# pactec_version_rev_A.net
KiCad netlist of a schematic drawn in EAGLE
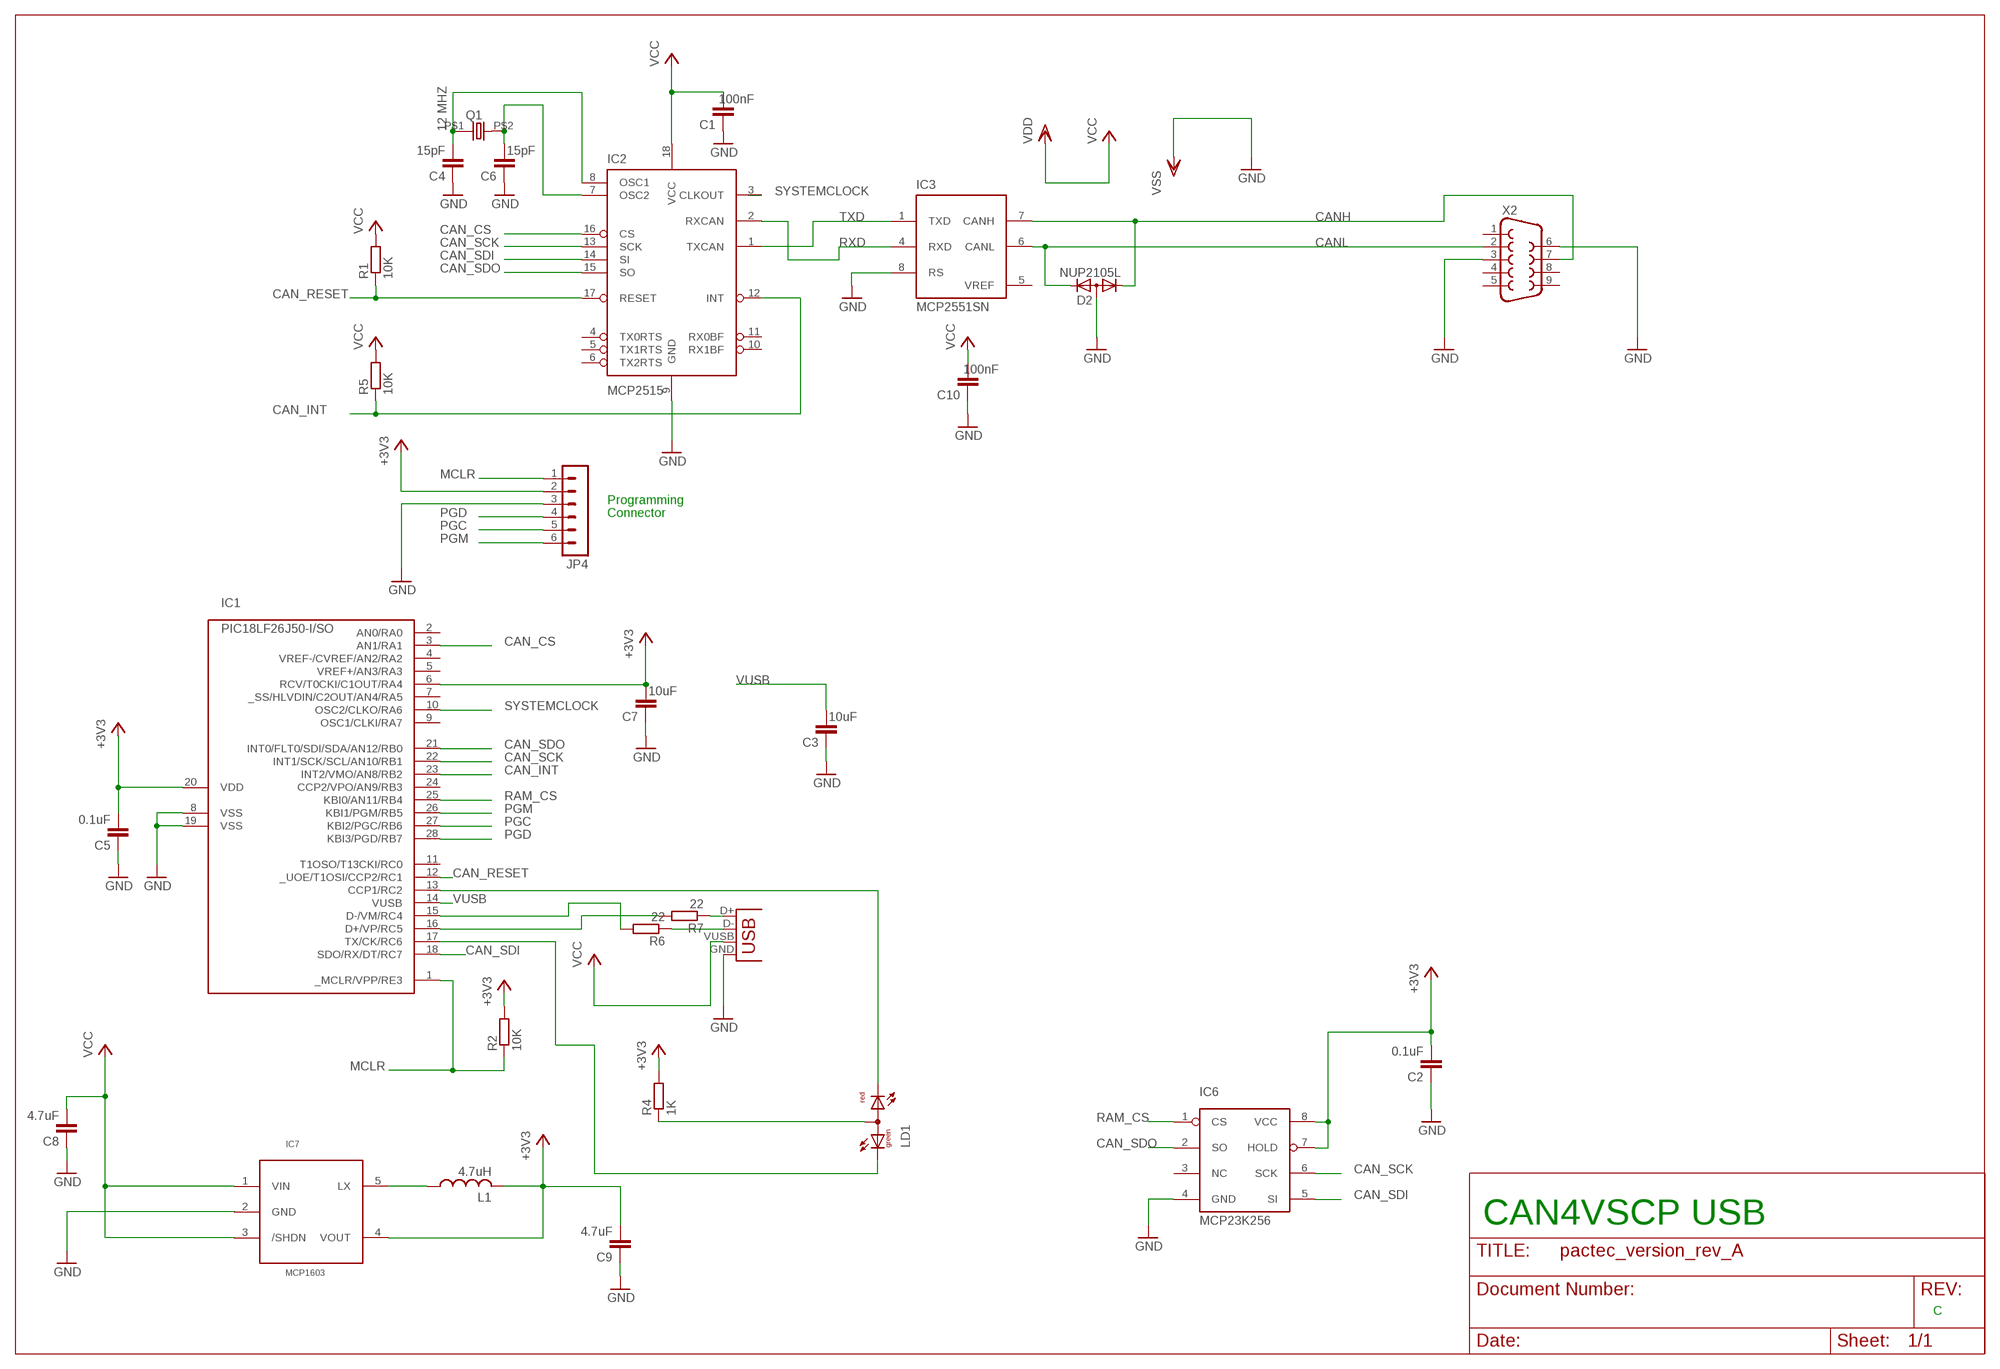
[diagram p0: schematic, sheet 1]

(export (version "E")
  (design (tool "Eeschema 10.0.6"))
  (components
    (comp (ref "C1")
      (value "100nF")
      (footprint "eagle-import:C0805")
      (libsource (lib "eagle-import") (part "C-EUC0805"))
    )
    (comp (ref "C2")
      (value "0.1uF")
      (footprint "eagle-import:C0805")
      (libsource (lib "eagle-import") (part "C-EUC0805"))
    )
    (comp (ref "C3")
      (value "10uF")
      (footprint "eagle-import:C0805")
      (libsource (lib "eagle-import") (part "C-EUC0805"))
    )
    (comp (ref "C4")
      (value "15pF")
      (footprint "eagle-import:C0805")
      (libsource (lib "eagle-import") (part "C-EUC0805"))
    )
    (comp (ref "C5")
      (value "0.1uF")
      (footprint "eagle-import:C0805")
      (libsource (lib "eagle-import") (part "C-EUC0805"))
    )
    (comp (ref "C6")
      (value "15pF")
      (footprint "eagle-import:C0805")
      (libsource (lib "eagle-import") (part "C-EUC0805"))
    )
    (comp (ref "C7")
      (value "10uF")
      (footprint "eagle-import:C0805")
      (libsource (lib "eagle-import") (part "C-EUC0805"))
    )
    (comp (ref "C8")
      (value "4.7uF")
      (footprint "eagle-import:C0805")
      (libsource (lib "eagle-import") (part "C-EUC0805"))
    )
    (comp (ref "C9")
      (value "4.7uF")
      (footprint "eagle-import:C0805")
      (libsource (lib "eagle-import") (part "C-EUC0805"))
    )
    (comp (ref "C10")
      (value "100nF")
      (footprint "eagle-import:C0805")
      (libsource (lib "eagle-import") (part "C-EUC0805"))
    )
    (comp (ref "D2")
      (value "NUP2105L")
      (footprint "eagle-import:SOT23")
      (libsource (lib "eagle-import") (part "DIODE-2CA|ACSOT23"))
    )
    (comp (ref "IC1")
      (value "PIC18LF26J50-I/SO")
      (footprint "eagle-import:SO-28W")
      (libsource (lib "eagle-import") (part "PIC182550-I/SOLF"))
    )
    (comp (ref "IC2")
      (value "MCP2515")
      (footprint "eagle-import:SO-18W")
      (libsource (lib "eagle-import") (part "MCP2515"))
    )
    (comp (ref "IC3")
      (value "MCP2551SN")
      (footprint "eagle-import:SO-08")
      (libsource (lib "eagle-import") (part "MCP2551SN"))
    )
    (comp (ref "IC6")
      (value "MCP23K256")
      (footprint "eagle-import:SO-8")
      (libsource (lib "eagle-import") (part "MCP23A256"))
    )
    (comp (ref "IC7")
      (value "MCP1603")
      (footprint "eagle-import:SOT23-5L")
      (libsource (lib "eagle-import") (part "MCP1603"))
    )
    (comp (ref "J4")
      (value "USB-B-S")
      (footprint "eagle-import:USB-B-SMT")
      (libsource (lib "eagle-import") (part "USB-B-S"))
    )
    (comp (ref "JP4")
      (value "MA06-1")
      (footprint "eagle-import:MA06-1")
      (libsource (lib "eagle-import") (part "MA06-1"))
    )
    (comp (ref "L1")
      (value "4.7uH")
      (footprint "eagle-import:L2012C")
      (libsource (lib "eagle-import") (part "L-USL2012C"))
    )
    (comp (ref "LD1")
      (value "DUOLED-RG-A")
      (footprint "eagle-import:DUOLED-A-5MM")
      (libsource (lib "eagle-import") (part "DUOLED-RG-A"))
    )
    (comp (ref "Q1")
      (value "12 MHZ")
      (footprint "eagle-import:9C")
      (libsource (lib "eagle-import") (part "HC-49S"))
    )
    (comp (ref "R1")
      (value "10K")
      (footprint "eagle-import:R0805")
      (libsource (lib "eagle-import") (part "R-EU_R0805"))
    )
    (comp (ref "R2")
      (value "10K")
      (footprint "eagle-import:R0805")
      (libsource (lib "eagle-import") (part "R-EU_R0805"))
    )
    (comp (ref "R4")
      (value "1K")
      (footprint "eagle-import:R0805")
      (libsource (lib "eagle-import") (part "R-EU_R0805"))
    )
    (comp (ref "R5")
      (value "10K")
      (footprint "eagle-import:R0805")
      (libsource (lib "eagle-import") (part "R-EU_R0805"))
    )
    (comp (ref "R6")
      (value "22")
      (footprint "eagle-import:R0805")
      (libsource (lib "eagle-import") (part "R-EU_R0805"))
    )
    (comp (ref "R7")
      (value "22")
      (footprint "eagle-import:R0805")
      (libsource (lib "eagle-import") (part "R-EU_R0805"))
    )
    (comp (ref "X2")
      (value "DB9MALE")
      (footprint "eagle-import:DB9_MALE")
      (libsource (lib "eagle-import") (part "DB9MALE"))
    )
  )
  (nets
    (net (code "1") (name "+3V3") (class "Default")
      (node (ref "C2") (pin "2") (pinfunction "2_2") (pintype "passive"))
      (node (ref "C5") (pin "2") (pinfunction "2_2") (pintype "passive"))
      (node (ref "C7") (pin "2") (pinfunction "2_2") (pintype "passive"))
      (node (ref "C9") (pin "2") (pinfunction "2_2") (pintype "passive"))
      (node (ref "IC1") (pin "20") (pinfunction "VDD_20") (pintype "power_in"))
      (node (ref "IC1") (pin "6") (pinfunction "RCV/T0CKI/C1OUT/RA4_6") (pintype "bidirectional"))
      (node (ref "IC6") (pin "7") (pinfunction "HOLD_7") (pintype "input"))
      (node (ref "IC6") (pin "8") (pinfunction "VCC_8") (pintype "power_in"))
      (node (ref "IC7") (pin "4") (pinfunction "VOUT_4") (pintype "bidirectional"))
      (node (ref "JP4") (pin "2") (pinfunction "2_2") (pintype "passive"))
      (node (ref "L1") (pin "2") (pinfunction "2_2") (pintype "passive"))
      (node (ref "R2") (pin "2") (pinfunction "2_2") (pintype "passive"))
      (node (ref "R4") (pin "2") (pinfunction "2_2") (pintype "passive"))
    )
    (net (code "2") (name "/CANH") (class "Default")
      (node (ref "D2") (pin "1") (pinfunction "K1_1") (pintype "passive"))
      (node (ref "IC3") (pin "7") (pinfunction "CANH_7") (pintype "bidirectional"))
      (node (ref "X2") (pin "7") (pinfunction "7_7") (pintype "passive"))
    )
    (net (code "3") (name "/CANL") (class "Default")
      (node (ref "D2") (pin "2") (pinfunction "K2_2") (pintype "passive"))
      (node (ref "IC3") (pin "6") (pinfunction "CANL_6") (pintype "bidirectional"))
      (node (ref "X2") (pin "2") (pinfunction "2_2") (pintype "passive"))
    )
    (net (code "4") (name "/CAN_CS") (class "Default")
      (node (ref "IC1") (pin "3") (pinfunction "AN1/RA1_3") (pintype "bidirectional"))
      (node (ref "IC2") (pin "16") (pinfunction "CS_16") (pintype "input"))
    )
    (net (code "5") (name "/CAN_INT") (class "Default")
      (node (ref "IC1") (pin "23") (pinfunction "INT2/VMO/AN8/RB2_23") (pintype "bidirectional"))
      (node (ref "IC2") (pin "12") (pinfunction "INT_12") (pintype "output"))
      (node (ref "R5") (pin "1") (pinfunction "1_1") (pintype "passive"))
    )
    (net (code "6") (name "/CAN_RESET") (class "Default")
      (node (ref "IC1") (pin "12") (pinfunction "_UOE/T1OSI/CCP2/RC1_12") (pintype "bidirectional"))
      (node (ref "IC2") (pin "17") (pinfunction "RESET_17") (pintype "input"))
      (node (ref "R1") (pin "1") (pinfunction "1_1") (pintype "passive"))
    )
    (net (code "7") (name "/CAN_SCK") (class "Default")
      (node (ref "IC1") (pin "22") (pinfunction "INT1/SCK/SCL/AN10/RB1_22") (pintype "bidirectional"))
      (node (ref "IC2") (pin "13") (pinfunction "SCK_13") (pintype "input"))
      (node (ref "IC6") (pin "6") (pinfunction "SCK_6") (pintype "input"))
    )
    (net (code "8") (name "/CAN_SDI") (class "Default")
      (node (ref "IC1") (pin "18") (pinfunction "SDO/RX/DT/RC7_18") (pintype "bidirectional"))
      (node (ref "IC2") (pin "14") (pinfunction "SI_14") (pintype "input"))
      (node (ref "IC6") (pin "5") (pinfunction "SI_5") (pintype "input"))
    )
    (net (code "9") (name "/CAN_SDO") (class "Default")
      (node (ref "IC1") (pin "21") (pinfunction "INT0/FLT0/SDI/SDA/AN12/RB0_21") (pintype "bidirectional"))
      (node (ref "IC2") (pin "15") (pinfunction "SO_15") (pintype "output"))
      (node (ref "IC6") (pin "2") (pinfunction "SO_2") (pintype "output"))
    )
    (net (code "10") (name "/MCLR") (class "Default")
      (node (ref "IC1") (pin "1") (pinfunction "_MCLR/VPP/RE3_1") (pintype "input"))
      (node (ref "JP4") (pin "1") (pinfunction "1_1") (pintype "passive"))
      (node (ref "R2") (pin "1") (pinfunction "1_1") (pintype "passive"))
    )
    (net (code "11") (name "/PGC") (class "Default")
      (node (ref "IC1") (pin "27") (pinfunction "KBI2/PGC/RB6_27") (pintype "bidirectional"))
      (node (ref "JP4") (pin "5") (pinfunction "5_5") (pintype "passive"))
    )
    (net (code "12") (name "/PGD") (class "Default")
      (node (ref "IC1") (pin "28") (pinfunction "KBI3/PGD/RB7_28") (pintype "bidirectional"))
      (node (ref "JP4") (pin "4") (pinfunction "4_4") (pintype "passive"))
    )
    (net (code "13") (name "/PGM") (class "Default")
      (node (ref "IC1") (pin "26") (pinfunction "KBI1/PGM/RB5_26") (pintype "bidirectional"))
      (node (ref "JP4") (pin "6") (pinfunction "6_6") (pintype "passive"))
    )
    (net (code "14") (name "/RAM_CS") (class "Default")
      (node (ref "IC1") (pin "25") (pinfunction "KBI0/AN11/RB4_25") (pintype "bidirectional"))
      (node (ref "IC6") (pin "1") (pinfunction "CS_1") (pintype "input"))
    )
    (net (code "15") (name "/RXD") (class "Default")
      (node (ref "IC2") (pin "2") (pinfunction "RXCAN_2") (pintype "input"))
      (node (ref "IC3") (pin "4") (pinfunction "RXD_4") (pintype "output"))
    )
    (net (code "16") (name "/SYSTEMCLOCK") (class "Default")
      (node (ref "IC1") (pin "10") (pinfunction "OSC2/CLKO/RA6_10") (pintype "bidirectional"))
      (node (ref "IC2") (pin "3") (pinfunction "CLKOUT_3") (pintype "output"))
    )
    (net (code "17") (name "/TXD") (class "Default")
      (node (ref "IC2") (pin "1") (pinfunction "TXCAN_1") (pintype "output"))
      (node (ref "IC3") (pin "1") (pinfunction "TXD_1") (pintype "input"))
    )
    (net (code "18") (name "/VREF") (class "Default")
      (node (ref "IC3") (pin "5") (pinfunction "VREF_5") (pintype "power_in"))
    )
    (net (code "19") (name "/VUSB") (class "Default")
      (node (ref "C3") (pin "2") (pinfunction "2_2") (pintype "passive"))
      (node (ref "IC1") (pin "14") (pinfunction "VUSB_14") (pintype "bidirectional"))
    )
    (net (code "20") (name "GND") (class "Default")
      (node (ref "C1") (pin "1") (pinfunction "1_1") (pintype "passive"))
      (node (ref "C10") (pin "1") (pinfunction "1_1") (pintype "passive"))
      (node (ref "C2") (pin "1") (pinfunction "1_1") (pintype "passive"))
      (node (ref "C3") (pin "1") (pinfunction "1_1") (pintype "passive"))
      (node (ref "C4") (pin "1") (pinfunction "1_1") (pintype "passive"))
      (node (ref "C5") (pin "1") (pinfunction "1_1") (pintype "passive"))
      (node (ref "C6") (pin "1") (pinfunction "1_1") (pintype "passive"))
      (node (ref "C7") (pin "1") (pinfunction "1_1") (pintype "passive"))
      (node (ref "C8") (pin "1") (pinfunction "1_1") (pintype "passive"))
      (node (ref "C9") (pin "1") (pinfunction "1_1") (pintype "passive"))
      (node (ref "D2") (pin "3") (pinfunction "A_3") (pintype "passive"))
      (node (ref "IC1") (pin "19") (pinfunction "VSS_19") (pintype "power_in"))
      (node (ref "IC1") (pin "8") (pinfunction "VSS_8") (pintype "power_in"))
      (node (ref "IC2") (pin "9") (pinfunction "GND_9") (pintype "power_in"))
      (node (ref "IC3") (pin "8") (pinfunction "RS_8") (pintype "input"))
      (node (ref "IC6") (pin "4") (pinfunction "GND_4") (pintype "power_in"))
      (node (ref "IC7") (pin "2") (pinfunction "GND_2") (pintype "power_in"))
      (node (ref "J4") (pin "GND") (pinfunction "GND_GND") (pintype "bidirectional"))
      (node (ref "JP4") (pin "3") (pinfunction "3_3") (pintype "passive"))
      (node (ref "X2") (pin "3") (pinfunction "3_3") (pintype "passive"))
      (node (ref "X2") (pin "6") (pinfunction "6_6") (pintype "passive"))
    )
    (net (code "21") (name "Net-(IC1-CCP1{slash}RC2)") (class "Default")
      (node (ref "IC1") (pin "13") (pinfunction "CCP1/RC2_13") (pintype "bidirectional"))
      (node (ref "LD1") (pin "CR") (pinfunction "CR_CR") (pintype "passive"))
    )
    (net (code "22") (name "Net-(IC1-D+{slash}VP{slash}RC5)") (class "Default")
      (node (ref "IC1") (pin "16") (pinfunction "D+/VP/RC5_16") (pintype "bidirectional"))
      (node (ref "R7") (pin "2") (pinfunction "2_2") (pintype "passive"))
    )
    (net (code "23") (name "Net-(IC1-D-{slash}VM{slash}RC4)") (class "Default")
      (node (ref "IC1") (pin "15") (pinfunction "D-/VM/RC4_15") (pintype "bidirectional"))
      (node (ref "R6") (pin "2") (pinfunction "2_2") (pintype "passive"))
    )
    (net (code "24") (name "Net-(IC1-TX{slash}CK{slash}RC6)") (class "Default")
      (node (ref "IC1") (pin "17") (pinfunction "TX/CK/RC6_17") (pintype "bidirectional"))
      (node (ref "LD1") (pin "CX") (pinfunction "CG_CX") (pintype "passive"))
    )
    (net (code "25") (name "Net-(IC2-OSC1)") (class "Default")
      (node (ref "C4") (pin "2") (pinfunction "2_2") (pintype "passive"))
      (node (ref "IC2") (pin "8") (pinfunction "OSC1_8") (pintype "input"))
      (node (ref "Q1") (pin "P$1") (pinfunction "1_P$1") (pintype "passive"))
    )
    (net (code "26") (name "Net-(IC2-OSC2)") (class "Default")
      (node (ref "C6") (pin "2") (pinfunction "2_2") (pintype "passive"))
      (node (ref "IC2") (pin "7") (pinfunction "OSC2_7") (pintype "output"))
      (node (ref "Q1") (pin "P$2") (pinfunction "2_P$2") (pintype "passive"))
    )
    (net (code "27") (name "Net-(IC7-LX)") (class "Default")
      (node (ref "IC7") (pin "5") (pinfunction "LX_5") (pintype "bidirectional"))
      (node (ref "L1") (pin "1") (pinfunction "1_1") (pintype "passive"))
    )
    (net (code "28") (name "Net-(J4-PadD+)") (class "Default")
      (node (ref "J4") (pin "D+") (pinfunction "D+_D+") (pintype "bidirectional"))
      (node (ref "R7") (pin "1") (pinfunction "1_1") (pintype "passive"))
    )
    (net (code "29") (name "Net-(J4-PadD-)") (class "Default")
      (node (ref "J4") (pin "D-") (pinfunction "D-_D-") (pintype "bidirectional"))
      (node (ref "R6") (pin "1") (pinfunction "1_1") (pintype "passive"))
    )
    (net (code "30") (name "Net-(LD1-PadA)") (class "Default")
      (node (ref "LD1") (pin "A") (pinfunction "A_A") (pintype "passive"))
      (node (ref "R4") (pin "1") (pinfunction "1_1") (pintype "passive"))
    )
    (net (code "31") (name "VCC") (class "Default")
      (node (ref "C1") (pin "2") (pinfunction "2_2") (pintype "passive"))
      (node (ref "C10") (pin "2") (pinfunction "2_2") (pintype "passive"))
      (node (ref "C8") (pin "2") (pinfunction "2_2") (pintype "passive"))
      (node (ref "IC2") (pin "18") (pinfunction "VCC_18") (pintype "power_in"))
      (node (ref "IC7") (pin "1") (pinfunction "VIN_1") (pintype "bidirectional"))
      (node (ref "IC7") (pin "3") (pinfunction "/SHDN_3") (pintype "bidirectional"))
      (node (ref "J4") (pin "VUSB") (pinfunction "VBUS_VUSB") (pintype "bidirectional"))
      (node (ref "R1") (pin "2") (pinfunction "2_2") (pintype "passive"))
      (node (ref "R5") (pin "2") (pinfunction "2_2") (pintype "passive"))
    )
    (net (code "32") (name "unconnected-(IC1-AN0{slash}RA0-Pad2)") (class "Default")
      (node (ref "IC1") (pin "2") (pinfunction "AN0/RA0_2") (pintype "bidirectional"))
    )
    (net (code "33") (name "unconnected-(IC1-CCP2{slash}VPO{slash}AN9{slash}RB3-Pad24)") (class "Default")
      (node (ref "IC1") (pin "24") (pinfunction "CCP2/VPO/AN9/RB3_24") (pintype "bidirectional"))
    )
    (net (code "34") (name "unconnected-(IC1-OSC1{slash}CLKI{slash}RA7-Pad9)") (class "Default")
      (node (ref "IC1") (pin "9") (pinfunction "OSC1/CLKI/RA7_9") (pintype "bidirectional"))
    )
    (net (code "35") (name "unconnected-(IC1-T1OSO{slash}T13CKI{slash}RC0-Pad11)") (class "Default")
      (node (ref "IC1") (pin "11") (pinfunction "T1OSO/T13CKI/RC0_11") (pintype "bidirectional"))
    )
    (net (code "36") (name "unconnected-(IC1-VREF+{slash}AN3{slash}RA3-Pad5)") (class "Default")
      (node (ref "IC1") (pin "5") (pinfunction "VREF+/AN3/RA3_5") (pintype "bidirectional"))
    )
    (net (code "37") (name "unconnected-(IC1-VREF-{slash}CVREF{slash}AN2{slash}RA2-Pad4)") (class "Default")
      (node (ref "IC1") (pin "4") (pinfunction "VREF-/CVREF/AN2/RA2_4") (pintype "bidirectional"))
    )
    (net (code "38") (name "unconnected-(IC1-_SS{slash}HLVDIN{slash}C2OUT{slash}AN4{slash}RA5-Pad7)") (class "Default")
      (node (ref "IC1") (pin "7") (pinfunction "_SS/HLVDIN/C2OUT/AN4/RA5_7") (pintype "bidirectional"))
    )
    (net (code "39") (name "unconnected-(IC2-RX0BF-Pad11)") (class "Default")
      (node (ref "IC2") (pin "11") (pinfunction "RX0BF_11") (pintype "output"))
    )
    (net (code "40") (name "unconnected-(IC2-RX1BF-Pad10)") (class "Default")
      (node (ref "IC2") (pin "10") (pinfunction "RX1BF_10") (pintype "output"))
    )
    (net (code "41") (name "unconnected-(IC2-TX0RTS-Pad4)") (class "Default")
      (node (ref "IC2") (pin "4") (pinfunction "TX0RTS_4") (pintype "input"))
    )
    (net (code "42") (name "unconnected-(IC2-TX1RTS-Pad5)") (class "Default")
      (node (ref "IC2") (pin "5") (pinfunction "TX1RTS_5") (pintype "input"))
    )
    (net (code "43") (name "unconnected-(IC2-TX2RTS-Pad6)") (class "Default")
      (node (ref "IC2") (pin "6") (pinfunction "TX2RTS_6") (pintype "input"))
    )
    (net (code "44") (name "unconnected-(IC6-NC-Pad3)") (class "Default")
      (node (ref "IC6") (pin "3") (pinfunction "NC_3") (pintype "no_connect"))
    )
    (net (code "45") (name "unconnected-(X2-Pad1)") (class "Default")
      (node (ref "X2") (pin "1") (pinfunction "1_1") (pintype "passive"))
    )
    (net (code "46") (name "unconnected-(X2-Pad4)") (class "Default")
      (node (ref "X2") (pin "4") (pinfunction "4_4") (pintype "passive"))
    )
    (net (code "47") (name "unconnected-(X2-Pad5)") (class "Default")
      (node (ref "X2") (pin "5") (pinfunction "5_5") (pintype "passive"))
    )
    (net (code "48") (name "unconnected-(X2-Pad8)") (class "Default")
      (node (ref "X2") (pin "8") (pinfunction "8_8") (pintype "passive"))
    )
    (net (code "49") (name "unconnected-(X2-Pad9)") (class "Default")
      (node (ref "X2") (pin "9") (pinfunction "9_9") (pintype "passive"))
    )
  )
)
